# BME680_Breakout.net
KiCad netlist of a schematic drawn in EAGLE
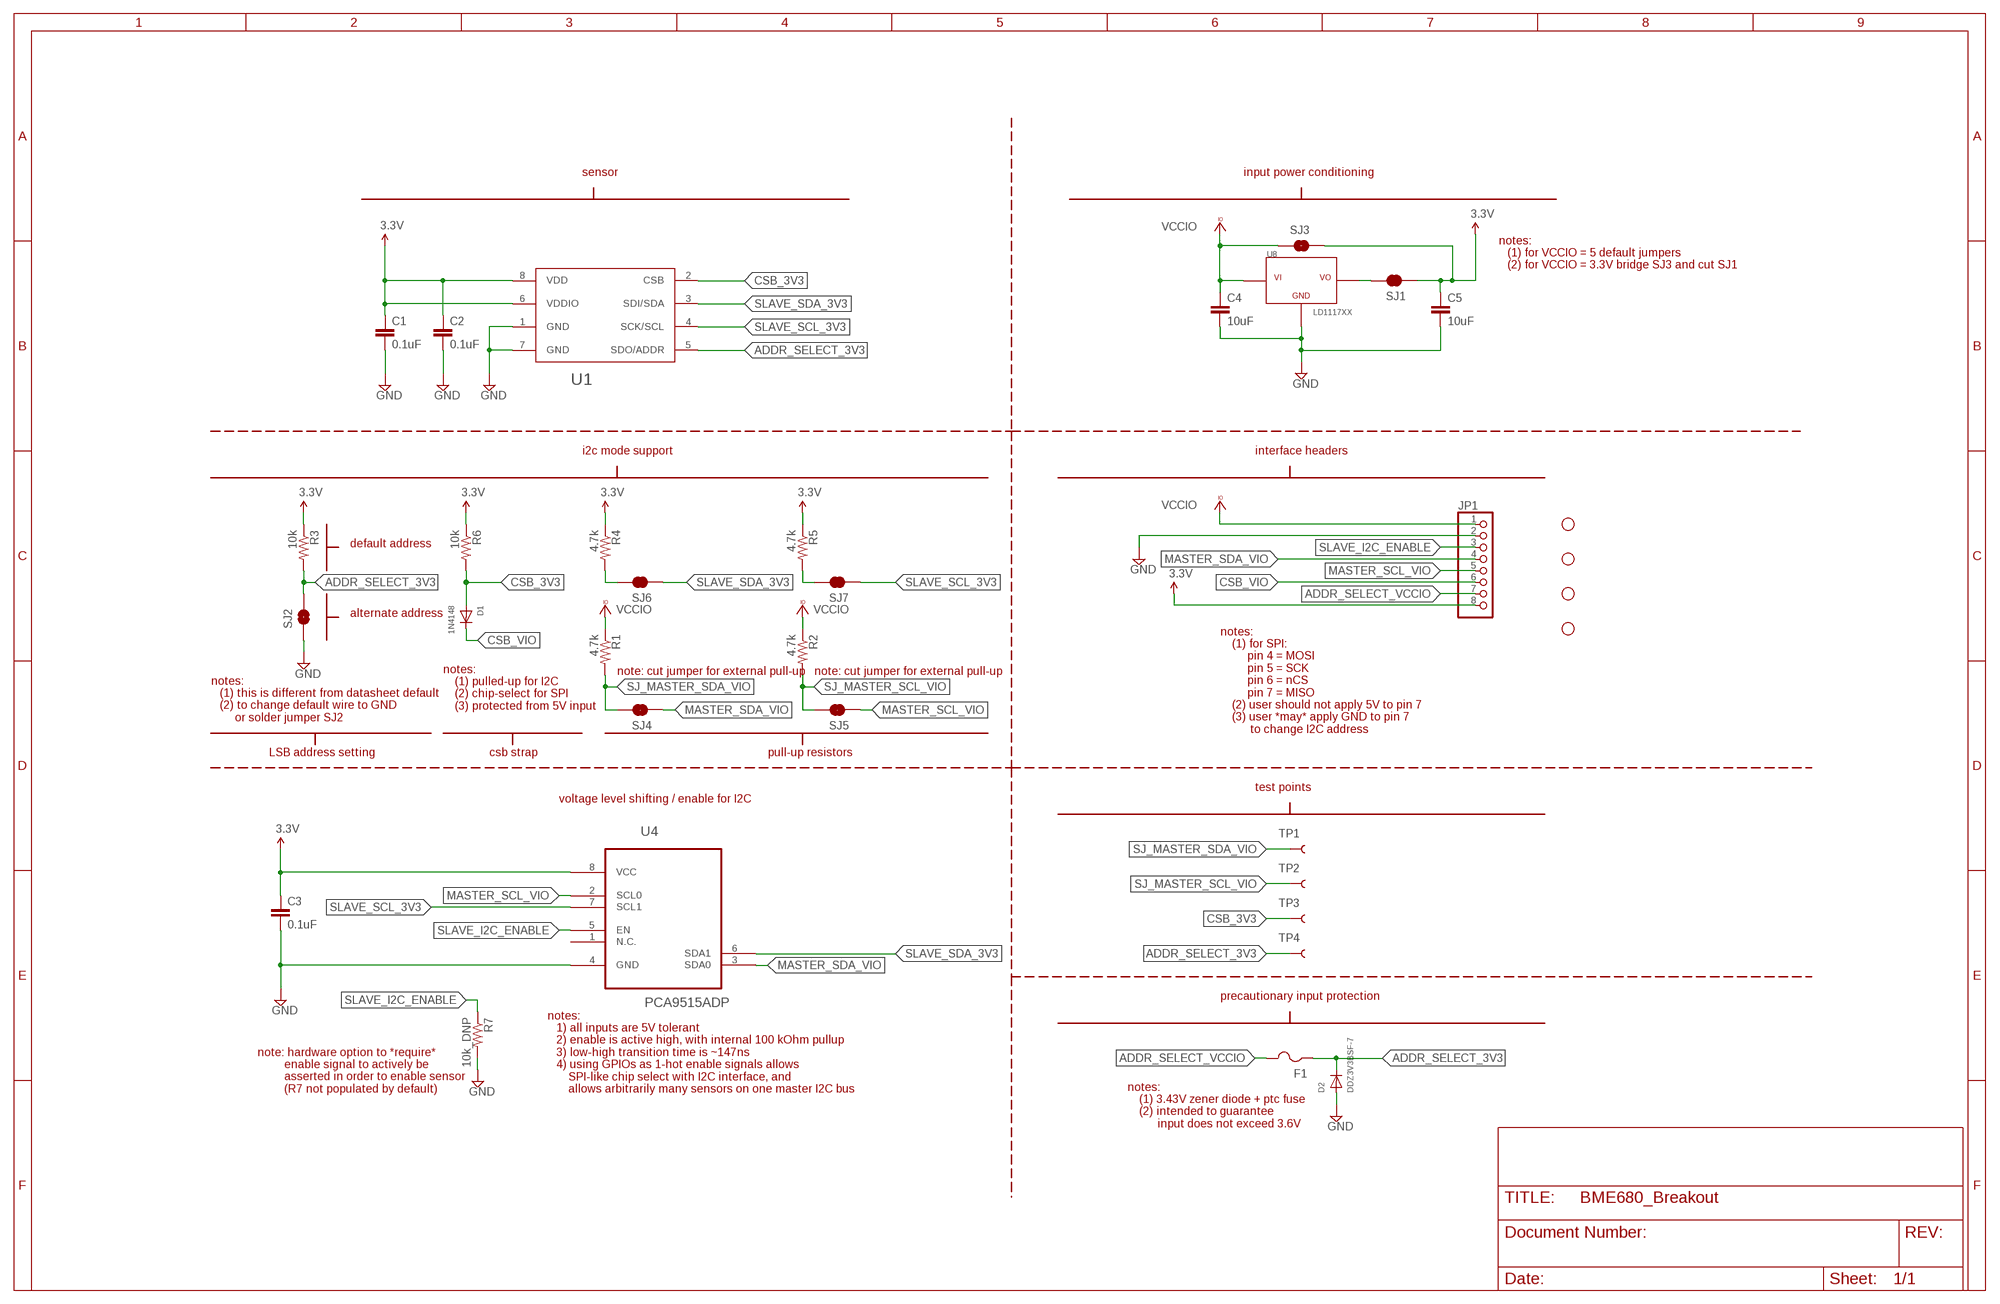
[diagram p0: schematic, sheet 1]

(export (version "E")
  (design (tool "Eeschema 10.0.6"))
  (components
    (comp (ref "C1")
      (value "0.1uF")
      (footprint "eagle-import:0805")
      (libsource (lib "eagle-import") (part "CAP0805"))
    )
    (comp (ref "C2")
      (value "0.1uF")
      (footprint "eagle-import:0805")
      (libsource (lib "eagle-import") (part "CAP0805"))
    )
    (comp (ref "C3")
      (value "0.1uF")
      (footprint "eagle-import:0805")
      (libsource (lib "eagle-import") (part "CAP0805"))
    )
    (comp (ref "C4")
      (value "10uF")
      (footprint "eagle-import:0805")
      (libsource (lib "eagle-import") (part "CAP0805"))
    )
    (comp (ref "C5")
      (value "10uF")
      (footprint "eagle-import:0805")
      (libsource (lib "eagle-import") (part "CAP0805"))
    )
    (comp (ref "D1")
      (value "1N4148")
      (footprint "eagle-import:SOD-323F")
      (libsource (lib "eagle-import") (part "DIODESOD-323F"))
    )
    (comp (ref "D2")
      (value "DDZ3V3BSF-7")
      (footprint "eagle-import:SOD-323F")
      (libsource (lib "eagle-import") (part "DIODESOD-323F"))
    )
    (comp (ref "F1")
      (value "PTCFUSE-1812")
      (footprint "eagle-import:1812")
      (libsource (lib "eagle-import") (part "PTCFUSE-1812"))
    )
    (comp (ref "JP1")
      (value "PINHD-1X8")
      (footprint "eagle-import:1X08")
      (libsource (lib "eagle-import") (part "PINHD-1X8"))
    )
    (comp (ref "R1")
      (value "4.7k")
      (footprint "eagle-import:0805")
      (libsource (lib "eagle-import") (part "RESISTOR0805-RES"))
    )
    (comp (ref "R2")
      (value "4.7k")
      (footprint "eagle-import:0805")
      (libsource (lib "eagle-import") (part "RESISTOR0805-RES"))
    )
    (comp (ref "R3")
      (value "10k")
      (footprint "eagle-import:0805")
      (libsource (lib "eagle-import") (part "RESISTOR0805-RES"))
    )
    (comp (ref "R4")
      (value "4.7k")
      (footprint "eagle-import:0805")
      (libsource (lib "eagle-import") (part "RESISTOR0805-RES"))
    )
    (comp (ref "R5")
      (value "4.7k")
      (footprint "eagle-import:0805")
      (libsource (lib "eagle-import") (part "RESISTOR0805-RES"))
    )
    (comp (ref "R6")
      (value "10k")
      (footprint "eagle-import:0805")
      (libsource (lib "eagle-import") (part "RESISTOR0805-RES"))
    )
    (comp (ref "R7")
      (value "10k_DNP")
      (footprint "eagle-import:0805")
      (libsource (lib "eagle-import") (part "RESISTOR0805-RES"))
    )
    (comp (ref "SJ1")
      (value "JUMPER-PAD-2-NC_BY_TRACE")
      (footprint "eagle-import:PAD-JUMPER-2-NC_BY_TRACE_YES_SILK")
      (libsource (lib "eagle-import") (part "JUMPER-PAD-2-NC_BY_TRACE"))
    )
    (comp (ref "SJ2")
      (value "JUMPER-PAD-2-NOYES_SILK")
      (footprint "eagle-import:PAD-JUMPER-2-NO_YES_SILK")
      (libsource (lib "eagle-import") (part "JUMPER-PAD-2-NOYES_SILK"))
    )
    (comp (ref "SJ3")
      (value "SOLDERJUMPERNC2")
      (footprint "eagle-import:SJ_2S-NOTRACE")
      (libsource (lib "eagle-import") (part "SOLDERJUMPERNC2"))
    )
    (comp (ref "SJ4")
      (value "JUMPER-PAD-2-NC_BY_TRACE")
      (footprint "eagle-import:PAD-JUMPER-2-NC_BY_TRACE_YES_SILK")
      (libsource (lib "eagle-import") (part "JUMPER-PAD-2-NC_BY_TRACE"))
    )
    (comp (ref "SJ5")
      (value "JUMPER-PAD-2-NC_BY_TRACE")
      (footprint "eagle-import:PAD-JUMPER-2-NC_BY_TRACE_YES_SILK")
      (libsource (lib "eagle-import") (part "JUMPER-PAD-2-NC_BY_TRACE"))
    )
    (comp (ref "SJ6")
      (value "JUMPER-PAD-2-NC_BY_TRACE")
      (footprint "eagle-import:PAD-JUMPER-2-NC_BY_TRACE_YES_SILK")
      (libsource (lib "eagle-import") (part "JUMPER-PAD-2-NC_BY_TRACE"))
    )
    (comp (ref "SJ7")
      (value "JUMPER-PAD-2-NC_BY_TRACE")
      (footprint "eagle-import:PAD-JUMPER-2-NC_BY_TRACE_YES_SILK")
      (libsource (lib "eagle-import") (part "JUMPER-PAD-2-NC_BY_TRACE"))
    )
    (comp (ref "STANDOFF1")
      (value "STAND-OFF")
      (footprint "eagle-import:STAND-OFF")
      (libsource (lib "eagle-import") (part "STAND-OFF"))
    )
    (comp (ref "STANDOFF2")
      (value "STAND-OFF")
      (footprint "eagle-import:STAND-OFF")
      (libsource (lib "eagle-import") (part "STAND-OFF"))
    )
    (comp (ref "STANDOFF3")
      (value "STAND-OFF")
      (footprint "eagle-import:STAND-OFF")
      (libsource (lib "eagle-import") (part "STAND-OFF"))
    )
    (comp (ref "STANDOFF4")
      (value "STAND-OFF")
      (footprint "eagle-import:STAND-OFF")
      (libsource (lib "eagle-import") (part "STAND-OFF"))
    )
    (comp (ref "TP1")
      (value "TEST-POINT3X4")
      (footprint "eagle-import:PAD.03X.04")
      (libsource (lib "eagle-import") (part "TEST-POINT3X4"))
    )
    (comp (ref "TP2")
      (value "TEST-POINT3X4")
      (footprint "eagle-import:PAD.03X.04")
      (libsource (lib "eagle-import") (part "TEST-POINT3X4"))
    )
    (comp (ref "TP3")
      (value "TEST-POINT3X4")
      (footprint "eagle-import:PAD.03X.04")
      (libsource (lib "eagle-import") (part "TEST-POINT3X4"))
    )
    (comp (ref "TP4")
      (value "TEST-POINT3X4")
      (footprint "eagle-import:PAD.03X.04")
      (libsource (lib "eagle-import") (part "TEST-POINT3X4"))
    )
    (comp (ref "U1")
      (value "BME680")
      (footprint "eagle-import:BME680")
      (libsource (lib "eagle-import") (part "BME680"))
    )
    (comp (ref "U4")
      (value "PCA9515ADP")
      (footprint "eagle-import:SOT505-1")
      (libsource (lib "eagle-import") (part "PCA9515ADP"))
    )
    (comp (ref "U8")
      (value "LD1117XX")
      (footprint "eagle-import:DPAK")
      (libsource (lib "eagle-import") (part "LD1117XX"))
    )
  )
  (nets
    (net (code "1") (name "3.3V") (class "Default")
      (node (ref "C1") (pin "1") (pinfunction "1_1") (pintype "passive"))
      (node (ref "C2") (pin "1") (pinfunction "1_1") (pintype "passive"))
      (node (ref "C3") (pin "1") (pinfunction "1_1") (pintype "passive"))
      (node (ref "C5") (pin "1") (pinfunction "1_1") (pintype "passive"))
      (node (ref "JP1") (pin "8") (pinfunction "8_8") (pintype "passive"))
      (node (ref "R3") (pin "1") (pinfunction "1_1") (pintype "passive"))
      (node (ref "R4") (pin "1") (pinfunction "1_1") (pintype "passive"))
      (node (ref "R5") (pin "1") (pinfunction "1_1") (pintype "passive"))
      (node (ref "R6") (pin "1") (pinfunction "1_1") (pintype "passive"))
      (node (ref "SJ1") (pin "1") (pinfunction "1_1") (pintype "passive"))
      (node (ref "SJ3") (pin "2") (pinfunction "2_2") (pintype "passive"))
      (node (ref "U1") (pin "6") (pinfunction "VDDIO_6") (pintype "bidirectional"))
      (node (ref "U1") (pin "8") (pinfunction "VDD_8") (pintype "bidirectional"))
      (node (ref "U4") (pin "8") (pinfunction "VCC_8") (pintype "power_in"))
    )
    (net (code "2") (name "ADDR_SELECT_3V3") (class "Default")
      (node (ref "D2") (pin "C") (pinfunction "C_C") (pintype "passive"))
      (node (ref "F1") (pin "1") (pinfunction "1_1") (pintype "passive"))
      (node (ref "R3") (pin "2") (pinfunction "2_2") (pintype "passive"))
      (node (ref "SJ2") (pin "2") (pinfunction "2_2") (pintype "passive"))
      (node (ref "TP4") (pin "P$1") (pinfunction "1_P$1") (pintype "bidirectional"))
      (node (ref "U1") (pin "5") (pinfunction "SDO/ADDR_5") (pintype "bidirectional"))
    )
    (net (code "3") (name "ADDR_SELECT_VCCIO") (class "Default")
      (node (ref "F1") (pin "2") (pinfunction "2_2") (pintype "passive"))
      (node (ref "JP1") (pin "7") (pinfunction "7_7") (pintype "passive"))
    )
    (net (code "4") (name "CSB_3V3") (class "Default")
      (node (ref "D1") (pin "A") (pinfunction "A_A") (pintype "passive"))
      (node (ref "R6") (pin "2") (pinfunction "2_2") (pintype "passive"))
      (node (ref "TP3") (pin "P$1") (pinfunction "1_P$1") (pintype "bidirectional"))
      (node (ref "U1") (pin "2") (pinfunction "CSB_2") (pintype "bidirectional"))
    )
    (net (code "5") (name "CSB_VIO") (class "Default")
      (node (ref "D1") (pin "C") (pinfunction "C_C") (pintype "passive"))
      (node (ref "JP1") (pin "6") (pinfunction "6_6") (pintype "passive"))
    )
    (net (code "6") (name "GND") (class "Default")
      (node (ref "C1") (pin "2") (pinfunction "2_2") (pintype "passive"))
      (node (ref "C2") (pin "2") (pinfunction "2_2") (pintype "passive"))
      (node (ref "C3") (pin "2") (pinfunction "2_2") (pintype "passive"))
      (node (ref "C4") (pin "2") (pinfunction "2_2") (pintype "passive"))
      (node (ref "C5") (pin "2") (pinfunction "2_2") (pintype "passive"))
      (node (ref "D2") (pin "A") (pinfunction "A_A") (pintype "passive"))
      (node (ref "JP1") (pin "2") (pinfunction "2_2") (pintype "passive"))
      (node (ref "R7") (pin "2") (pinfunction "2_2") (pintype "passive"))
      (node (ref "SJ2") (pin "1") (pinfunction "1_1") (pintype "passive"))
      (node (ref "U1") (pin "1") (pinfunction "GND_1") (pintype "bidirectional"))
      (node (ref "U1") (pin "7") (pinfunction "GND_7") (pintype "bidirectional"))
      (node (ref "U4") (pin "4") (pinfunction "GND_4") (pintype "passive"))
      (node (ref "U8") (pin "1") (pinfunction "GND_1") (pintype "power_in"))
    )
    (net (code "7") (name "MASTER_SCL_VIO") (class "Default")
      (node (ref "JP1") (pin "5") (pinfunction "5_5") (pintype "passive"))
      (node (ref "SJ5") (pin "1") (pinfunction "1_1") (pintype "passive"))
      (node (ref "U4") (pin "2") (pinfunction "SCL0_2") (pintype "bidirectional"))
    )
    (net (code "8") (name "MASTER_SDA_VIO") (class "Default")
      (node (ref "JP1") (pin "4") (pinfunction "4_4") (pintype "passive"))
      (node (ref "SJ4") (pin "1") (pinfunction "1_1") (pintype "passive"))
      (node (ref "U4") (pin "3") (pinfunction "SDA0_3") (pintype "bidirectional"))
    )
    (net (code "9") (name "Net-(R4-Pad2)") (class "Default")
      (node (ref "R4") (pin "2") (pinfunction "2_2") (pintype "passive"))
      (node (ref "SJ6") (pin "2") (pinfunction "2_2") (pintype "passive"))
    )
    (net (code "10") (name "Net-(R5-Pad2)") (class "Default")
      (node (ref "R5") (pin "2") (pinfunction "2_2") (pintype "passive"))
      (node (ref "SJ7") (pin "2") (pinfunction "2_2") (pintype "passive"))
    )
    (net (code "11") (name "Net-(U8-VO)") (class "Default")
      (node (ref "SJ1") (pin "2") (pinfunction "2_2") (pintype "passive"))
      (node (ref "U8") (pin "4") (pinfunction "VO_4") (pintype "power_in"))
    )
    (net (code "12") (name "SJ_MASTER_SCL_VIO") (class "Default")
      (node (ref "R2") (pin "2") (pinfunction "2_2") (pintype "passive"))
      (node (ref "SJ5") (pin "2") (pinfunction "2_2") (pintype "passive"))
      (node (ref "TP2") (pin "P$1") (pinfunction "1_P$1") (pintype "bidirectional"))
    )
    (net (code "13") (name "SJ_MASTER_SDA_VIO") (class "Default")
      (node (ref "R1") (pin "2") (pinfunction "2_2") (pintype "passive"))
      (node (ref "SJ4") (pin "2") (pinfunction "2_2") (pintype "passive"))
      (node (ref "TP1") (pin "P$1") (pinfunction "1_P$1") (pintype "bidirectional"))
    )
    (net (code "14") (name "SLAVE_I2C_ENABLE") (class "Default")
      (node (ref "JP1") (pin "3") (pinfunction "3_3") (pintype "passive"))
      (node (ref "R7") (pin "1") (pinfunction "1_1") (pintype "passive"))
      (node (ref "U4") (pin "5") (pinfunction "EN_5") (pintype "input"))
    )
    (net (code "15") (name "SLAVE_SCL_3V3") (class "Default")
      (node (ref "SJ7") (pin "1") (pinfunction "1_1") (pintype "passive"))
      (node (ref "U1") (pin "4") (pinfunction "SCK/SCL_4") (pintype "bidirectional"))
      (node (ref "U4") (pin "7") (pinfunction "SCL1_7") (pintype "bidirectional"))
    )
    (net (code "16") (name "SLAVE_SDA_3V3") (class "Default")
      (node (ref "SJ6") (pin "1") (pinfunction "1_1") (pintype "passive"))
      (node (ref "U1") (pin "3") (pinfunction "SDI/SDA_3") (pintype "bidirectional"))
      (node (ref "U4") (pin "6") (pinfunction "SDA1_6") (pintype "bidirectional"))
    )
    (net (code "17") (name "VCCIO") (class "Default")
      (node (ref "C4") (pin "1") (pinfunction "1_1") (pintype "passive"))
      (node (ref "JP1") (pin "1") (pinfunction "1_1") (pintype "passive"))
      (node (ref "R1") (pin "1") (pinfunction "1_1") (pintype "passive"))
      (node (ref "R2") (pin "1") (pinfunction "1_1") (pintype "passive"))
      (node (ref "SJ3") (pin "1") (pinfunction "1_1") (pintype "passive"))
      (node (ref "U8") (pin "3") (pinfunction "VI_3") (pintype "power_in"))
    )
    (net (code "18") (name "unconnected-(U4-N.C.-Pad1)") (class "Default")
      (node (ref "U4") (pin "1") (pinfunction "N.C._1") (pintype "no_connect"))
    )
  )
)
